# uav_pantilt.net
KiCad netlist of a schematic drawn in EAGLE
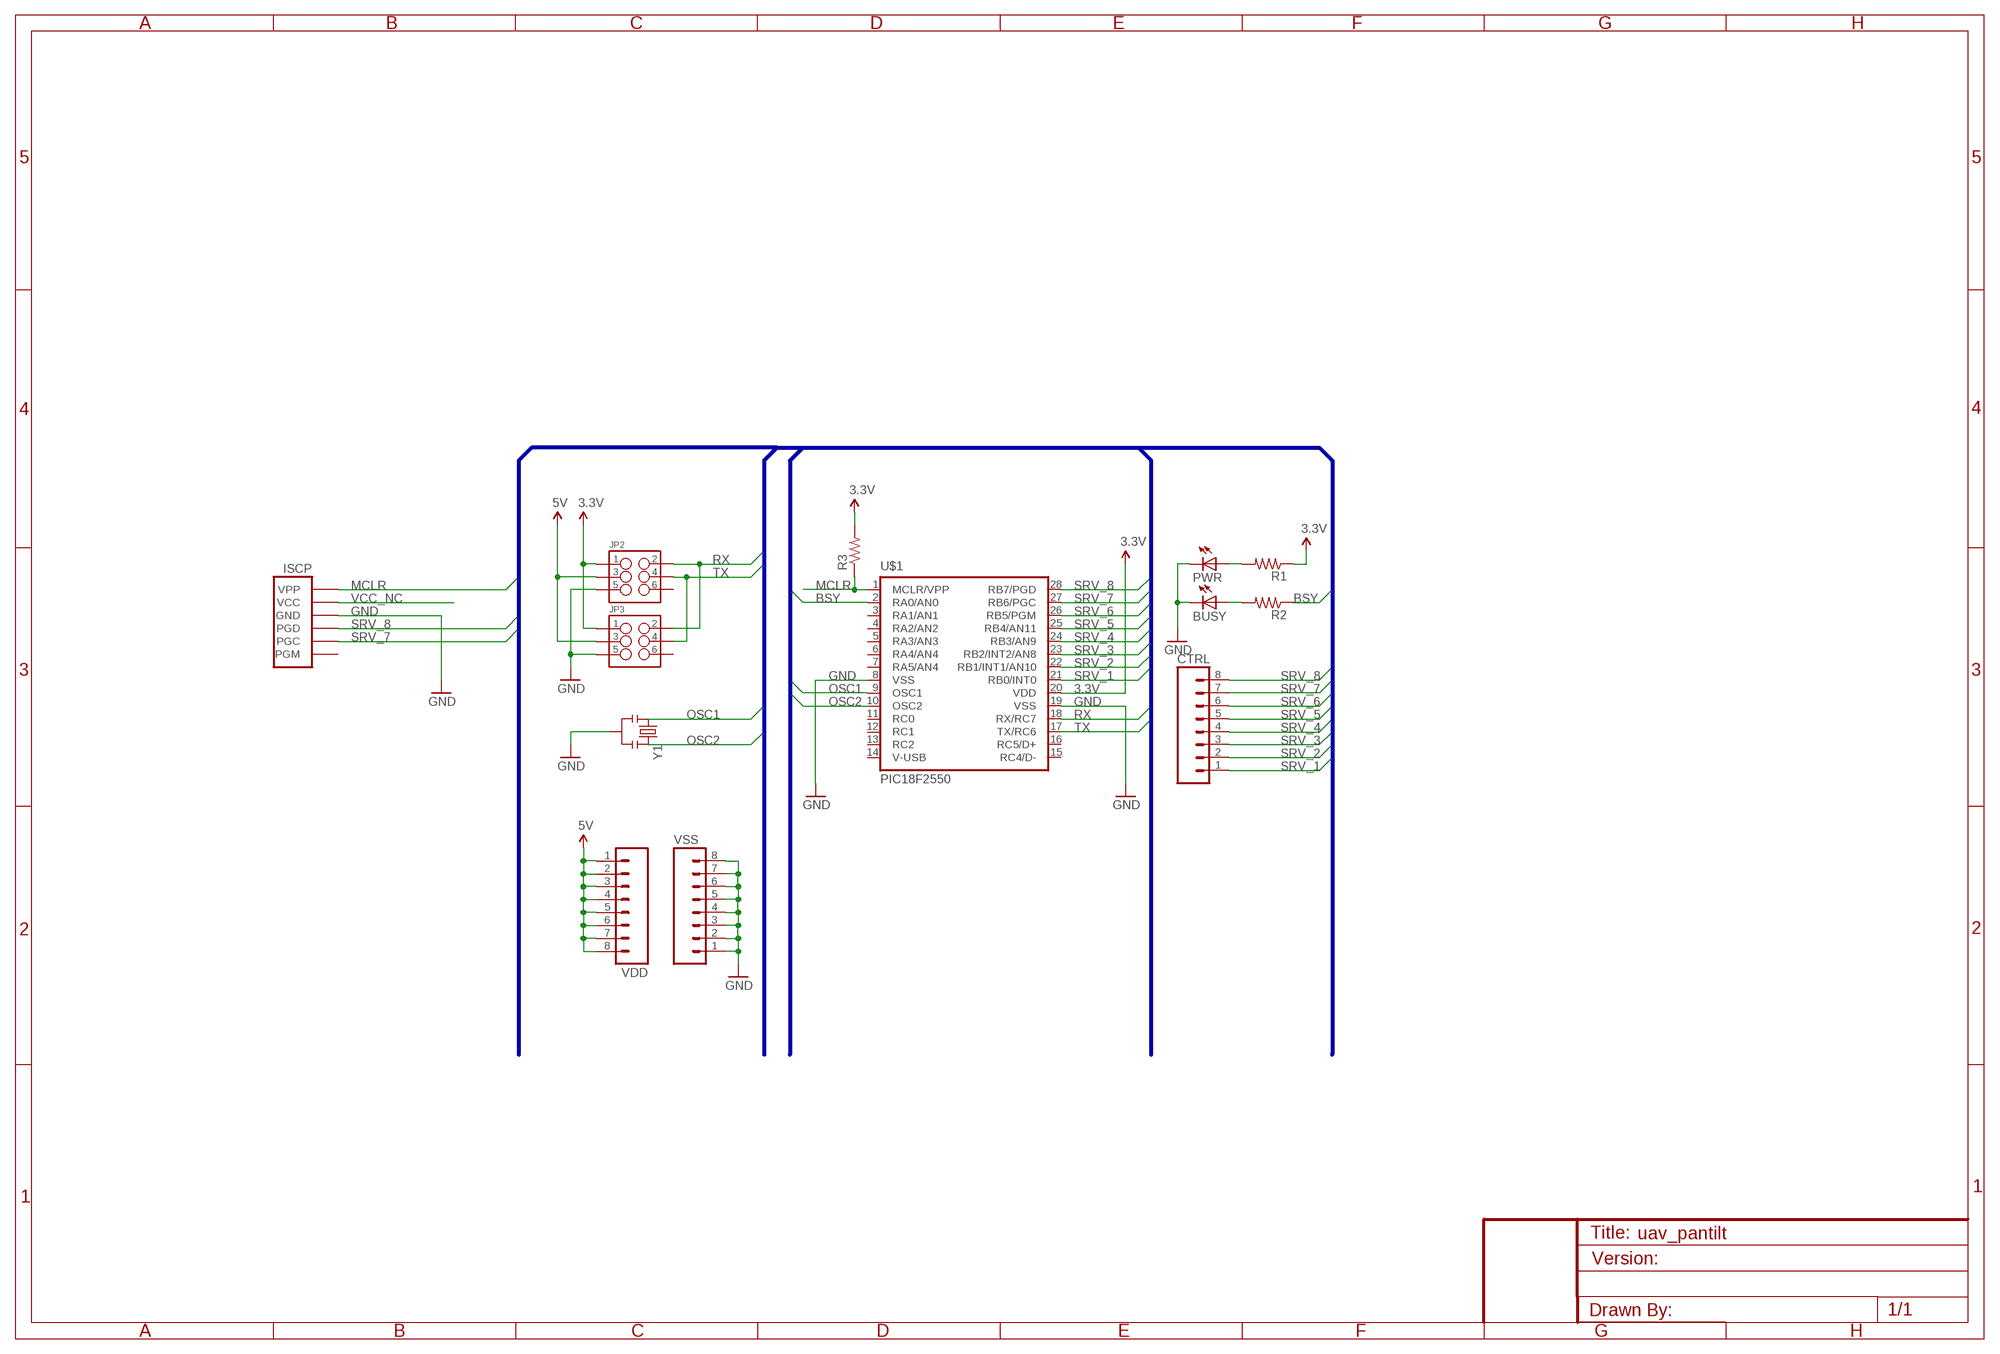
[diagram p0: schematic, sheet 1]

(export (version "E")
  (design (tool "Eeschema 10.0.6"))
  (components
    (comp (ref "BUSY")
      (value "LED5MM")
      (footprint "eagle-import:LED5MM")
      (libsource (lib "eagle-import") (part "LED5MM"))
    )
    (comp (ref "CTRL")
      (value "M08LOCK")
      (footprint "eagle-import:1X08_LOCK")
      (libsource (lib "eagle-import") (part "M08LOCK"))
    )
    (comp (ref "ISCP")
      (value "PIC-ICSPPOLAR_LOCK")
      (footprint "eagle-import:MOLEX-1X6_LOCK")
      (libsource (lib "eagle-import") (part "PIC-ICSPPOLAR_LOCK"))
    )
    (comp (ref "JP2")
      (value "M03X2")
      (footprint "eagle-import:2X3-SHROUDED")
      (libsource (lib "eagle-import") (part "M03X2"))
    )
    (comp (ref "JP3")
      (value "M03X2")
      (footprint "eagle-import:2X3-SHROUDED")
      (libsource (lib "eagle-import") (part "M03X2"))
    )
    (comp (ref "PWR")
      (value "LED5MM")
      (footprint "eagle-import:LED5MM")
      (libsource (lib "eagle-import") (part "LED5MM"))
    )
    (comp (ref "R1")
      (value "RESISTORKIT")
      (footprint "eagle-import:AXIAL-0.3-KIT")
      (libsource (lib "eagle-import") (part "RESISTORKIT"))
    )
    (comp (ref "R2")
      (value "RESISTORKIT")
      (footprint "eagle-import:AXIAL-0.3-KIT")
      (libsource (lib "eagle-import") (part "RESISTORKIT"))
    )
    (comp (ref "R3")
      (value "RESISTORKIT")
      (footprint "eagle-import:AXIAL-0.3-KIT")
      (libsource (lib "eagle-import") (part "RESISTORKIT"))
    )
    (comp (ref "U$1")
      (value "PIC18F2550")
      (footprint "eagle-import:DIL28-3")
      (libsource (lib "eagle-import") (part "PIC18F2550"))
    )
    (comp (ref "VDD")
      (value "M08LOCK")
      (footprint "eagle-import:1X08_LOCK")
      (libsource (lib "eagle-import") (part "M08LOCK"))
    )
    (comp (ref "VSS")
      (value "M08LOCK")
      (footprint "eagle-import:1X08_LOCK")
      (libsource (lib "eagle-import") (part "M08LOCK"))
    )
    (comp (ref "Y1")
      (value "RESONATORPTH")
      (footprint "eagle-import:RESONATOR-PTH")
      (libsource (lib "eagle-import") (part "RESONATORPTH"))
    )
  )
  (nets
    (net (code "1") (name "/BSY") (class "Default")
      (node (ref "R2") (pin "P$1") (pinfunction "1_P$1") (pintype "passive"))
      (node (ref "U$1") (pin "2") (pinfunction "RA0/AN0_2") (pintype "bidirectional"))
    )
    (net (code "2") (name "/MCLR") (class "Default")
      (node (ref "ISCP") (pin "6") (pinfunction "VPP_6") (pintype "bidirectional"))
      (node (ref "R3") (pin "P$1") (pinfunction "1_P$1") (pintype "passive"))
      (node (ref "U$1") (pin "1") (pinfunction "MCLR/VPP_1") (pintype "bidirectional"))
    )
    (net (code "3") (name "/OSC1") (class "Default")
      (node (ref "U$1") (pin "9") (pinfunction "OSC1_9") (pintype "bidirectional"))
      (node (ref "Y1") (pin "1") (pinfunction "1_1") (pintype "passive"))
    )
    (net (code "4") (name "/OSC2") (class "Default")
      (node (ref "U$1") (pin "10") (pinfunction "OSC2_10") (pintype "bidirectional"))
      (node (ref "Y1") (pin "3") (pinfunction "3_3") (pintype "passive"))
    )
    (net (code "5") (name "/RX") (class "Default")
      (node (ref "JP2") (pin "2") (pinfunction "2_2") (pintype "bidirectional"))
      (node (ref "JP3") (pin "2") (pinfunction "2_2") (pintype "bidirectional"))
      (node (ref "U$1") (pin "18") (pinfunction "RX/RC7_18") (pintype "input"))
    )
    (net (code "6") (name "/SRV_1") (class "Default")
      (node (ref "CTRL") (pin "1") (pinfunction "1_1") (pintype "passive"))
      (node (ref "U$1") (pin "21") (pinfunction "RB0/INT0_21") (pintype "bidirectional"))
    )
    (net (code "7") (name "/SRV_2") (class "Default")
      (node (ref "CTRL") (pin "2") (pinfunction "2_2") (pintype "passive"))
      (node (ref "U$1") (pin "22") (pinfunction "RB1/INT1/AN10_22") (pintype "bidirectional"))
    )
    (net (code "8") (name "/SRV_3") (class "Default")
      (node (ref "CTRL") (pin "3") (pinfunction "3_3") (pintype "passive"))
      (node (ref "U$1") (pin "23") (pinfunction "RB2/INT2/AN8_23") (pintype "bidirectional"))
    )
    (net (code "9") (name "/SRV_4") (class "Default")
      (node (ref "CTRL") (pin "4") (pinfunction "4_4") (pintype "passive"))
      (node (ref "U$1") (pin "24") (pinfunction "RB3/AN9_24") (pintype "bidirectional"))
    )
    (net (code "10") (name "/SRV_5") (class "Default")
      (node (ref "CTRL") (pin "5") (pinfunction "5_5") (pintype "passive"))
      (node (ref "U$1") (pin "25") (pinfunction "RB4/AN11_25") (pintype "bidirectional"))
    )
    (net (code "11") (name "/SRV_6") (class "Default")
      (node (ref "CTRL") (pin "6") (pinfunction "6_6") (pintype "passive"))
      (node (ref "U$1") (pin "26") (pinfunction "RB5/PGM_26") (pintype "bidirectional"))
    )
    (net (code "12") (name "/SRV_7") (class "Default")
      (node (ref "CTRL") (pin "7") (pinfunction "7_7") (pintype "passive"))
      (node (ref "ISCP") (pin "2") (pinfunction "PGC_2") (pintype "bidirectional"))
      (node (ref "U$1") (pin "27") (pinfunction "RB6/PGC_27") (pintype "bidirectional"))
    )
    (net (code "13") (name "/SRV_8") (class "Default")
      (node (ref "CTRL") (pin "8") (pinfunction "8_8") (pintype "passive"))
      (node (ref "ISCP") (pin "3") (pinfunction "PGD_3") (pintype "bidirectional"))
      (node (ref "U$1") (pin "28") (pinfunction "RB7/PGD_28") (pintype "bidirectional"))
    )
    (net (code "14") (name "/TX") (class "Default")
      (node (ref "JP2") (pin "4") (pinfunction "4_4") (pintype "bidirectional"))
      (node (ref "JP3") (pin "4") (pinfunction "4_4") (pintype "bidirectional"))
      (node (ref "U$1") (pin "17") (pinfunction "TX/RC6_17") (pintype "bidirectional"))
    )
    (net (code "15") (name "/VCC_NC") (class "Default")
      (node (ref "ISCP") (pin "5") (pinfunction "VCC_5") (pintype "bidirectional"))
    )
    (net (code "16") (name "3.3V") (class "Default")
      (node (ref "JP2") (pin "1") (pinfunction "1_1") (pintype "bidirectional"))
      (node (ref "JP3") (pin "1") (pinfunction "1_1") (pintype "bidirectional"))
      (node (ref "R1") (pin "P$1") (pinfunction "1_P$1") (pintype "passive"))
      (node (ref "R3") (pin "P$2") (pinfunction "2_P$2") (pintype "passive"))
      (node (ref "U$1") (pin "20") (pinfunction "VDD_20") (pintype "power_in"))
    )
    (net (code "17") (name "5V") (class "Default")
      (node (ref "JP2") (pin "3") (pinfunction "3_3") (pintype "bidirectional"))
      (node (ref "JP3") (pin "3") (pinfunction "3_3") (pintype "bidirectional"))
      (node (ref "VDD") (pin "1") (pinfunction "1_1") (pintype "passive"))
      (node (ref "VDD") (pin "2") (pinfunction "2_2") (pintype "passive"))
      (node (ref "VDD") (pin "3") (pinfunction "3_3") (pintype "passive"))
      (node (ref "VDD") (pin "4") (pinfunction "4_4") (pintype "passive"))
      (node (ref "VDD") (pin "5") (pinfunction "5_5") (pintype "passive"))
      (node (ref "VDD") (pin "6") (pinfunction "6_6") (pintype "passive"))
      (node (ref "VDD") (pin "7") (pinfunction "7_7") (pintype "passive"))
      (node (ref "VDD") (pin "8") (pinfunction "8_8") (pintype "passive"))
    )
    (net (code "18") (name "GND") (class "Default")
      (node (ref "BUSY") (pin "K") (pinfunction "C_K") (pintype "passive"))
      (node (ref "ISCP") (pin "4") (pinfunction "GND_4") (pintype "bidirectional"))
      (node (ref "JP2") (pin "5") (pinfunction "5_5") (pintype "bidirectional"))
      (node (ref "JP3") (pin "5") (pinfunction "5_5") (pintype "bidirectional"))
      (node (ref "PWR") (pin "K") (pinfunction "C_K") (pintype "passive"))
      (node (ref "U$1") (pin "19") (pinfunction "VSS_19") (pintype "power_in"))
      (node (ref "U$1") (pin "8") (pinfunction "VSS_8") (pintype "power_in"))
      (node (ref "VSS") (pin "1") (pinfunction "1_1") (pintype "passive"))
      (node (ref "VSS") (pin "2") (pinfunction "2_2") (pintype "passive"))
      (node (ref "VSS") (pin "3") (pinfunction "3_3") (pintype "passive"))
      (node (ref "VSS") (pin "4") (pinfunction "4_4") (pintype "passive"))
      (node (ref "VSS") (pin "5") (pinfunction "5_5") (pintype "passive"))
      (node (ref "VSS") (pin "6") (pinfunction "6_6") (pintype "passive"))
      (node (ref "VSS") (pin "7") (pinfunction "7_7") (pintype "passive"))
      (node (ref "VSS") (pin "8") (pinfunction "8_8") (pintype "passive"))
      (node (ref "Y1") (pin "2") (pinfunction "2_2") (pintype "passive"))
    )
    (net (code "19") (name "Net-(R1-2)") (class "Default")
      (node (ref "PWR") (pin "A") (pinfunction "A_A") (pintype "passive"))
      (node (ref "R1") (pin "P$2") (pinfunction "2_P$2") (pintype "passive"))
    )
    (net (code "20") (name "Net-(R2-2)") (class "Default")
      (node (ref "BUSY") (pin "A") (pinfunction "A_A") (pintype "passive"))
      (node (ref "R2") (pin "P$2") (pinfunction "2_P$2") (pintype "passive"))
    )
    (net (code "21") (name "unconnected-(ISCP-PGM-Pad1)") (class "Default")
      (node (ref "ISCP") (pin "1") (pinfunction "PGM_1") (pintype "bidirectional"))
    )
    (net (code "22") (name "unconnected-(JP2-Pad6)") (class "Default")
      (node (ref "JP2") (pin "6") (pinfunction "6_6") (pintype "bidirectional"))
    )
    (net (code "23") (name "unconnected-(JP3-Pad6)") (class "Default")
      (node (ref "JP3") (pin "6") (pinfunction "6_6") (pintype "bidirectional"))
    )
    (net (code "24") (name "unconnected-(U$1-RA1{slash}AN1-Pad3)") (class "Default")
      (node (ref "U$1") (pin "3") (pinfunction "RA1/AN1_3") (pintype "bidirectional"))
    )
    (net (code "25") (name "unconnected-(U$1-RA2{slash}AN2-Pad4)") (class "Default")
      (node (ref "U$1") (pin "4") (pinfunction "RA2/AN2_4") (pintype "bidirectional"))
    )
    (net (code "26") (name "unconnected-(U$1-RA3{slash}AN3-Pad5)") (class "Default")
      (node (ref "U$1") (pin "5") (pinfunction "RA3/AN3_5") (pintype "bidirectional"))
    )
    (net (code "27") (name "unconnected-(U$1-RA4{slash}AN4-Pad6)") (class "Default")
      (node (ref "U$1") (pin "6") (pinfunction "RA4/AN4_6") (pintype "bidirectional"))
    )
    (net (code "28") (name "unconnected-(U$1-RA5{slash}AN4-Pad7)") (class "Default")
      (node (ref "U$1") (pin "7") (pinfunction "RA5/AN4_7") (pintype "bidirectional"))
    )
    (net (code "29") (name "unconnected-(U$1-RC0-Pad11)") (class "Default")
      (node (ref "U$1") (pin "11") (pinfunction "RC0_11") (pintype "bidirectional"))
    )
    (net (code "30") (name "unconnected-(U$1-RC1-Pad12)") (class "Default")
      (node (ref "U$1") (pin "12") (pinfunction "RC1_12") (pintype "bidirectional"))
    )
    (net (code "31") (name "unconnected-(U$1-RC2-Pad13)") (class "Default")
      (node (ref "U$1") (pin "13") (pinfunction "RC2_13") (pintype "bidirectional"))
    )
    (net (code "32") (name "unconnected-(U$1-RC4{slash}D--Pad15)") (class "Default")
      (node (ref "U$1") (pin "15") (pinfunction "RC4/D-_15") (pintype "bidirectional"))
    )
    (net (code "33") (name "unconnected-(U$1-RC5{slash}D+-Pad16)") (class "Default")
      (node (ref "U$1") (pin "16") (pinfunction "RC5/D+_16") (pintype "bidirectional"))
    )
    (net (code "34") (name "unconnected-(U$1-V-USB-Pad14)") (class "Default")
      (node (ref "U$1") (pin "14") (pinfunction "V-USB_14") (pintype "bidirectional"))
    )
  )
)
